# e-Tapperhandpiece18.net
KiCad netlist of a schematic drawn in EAGLE
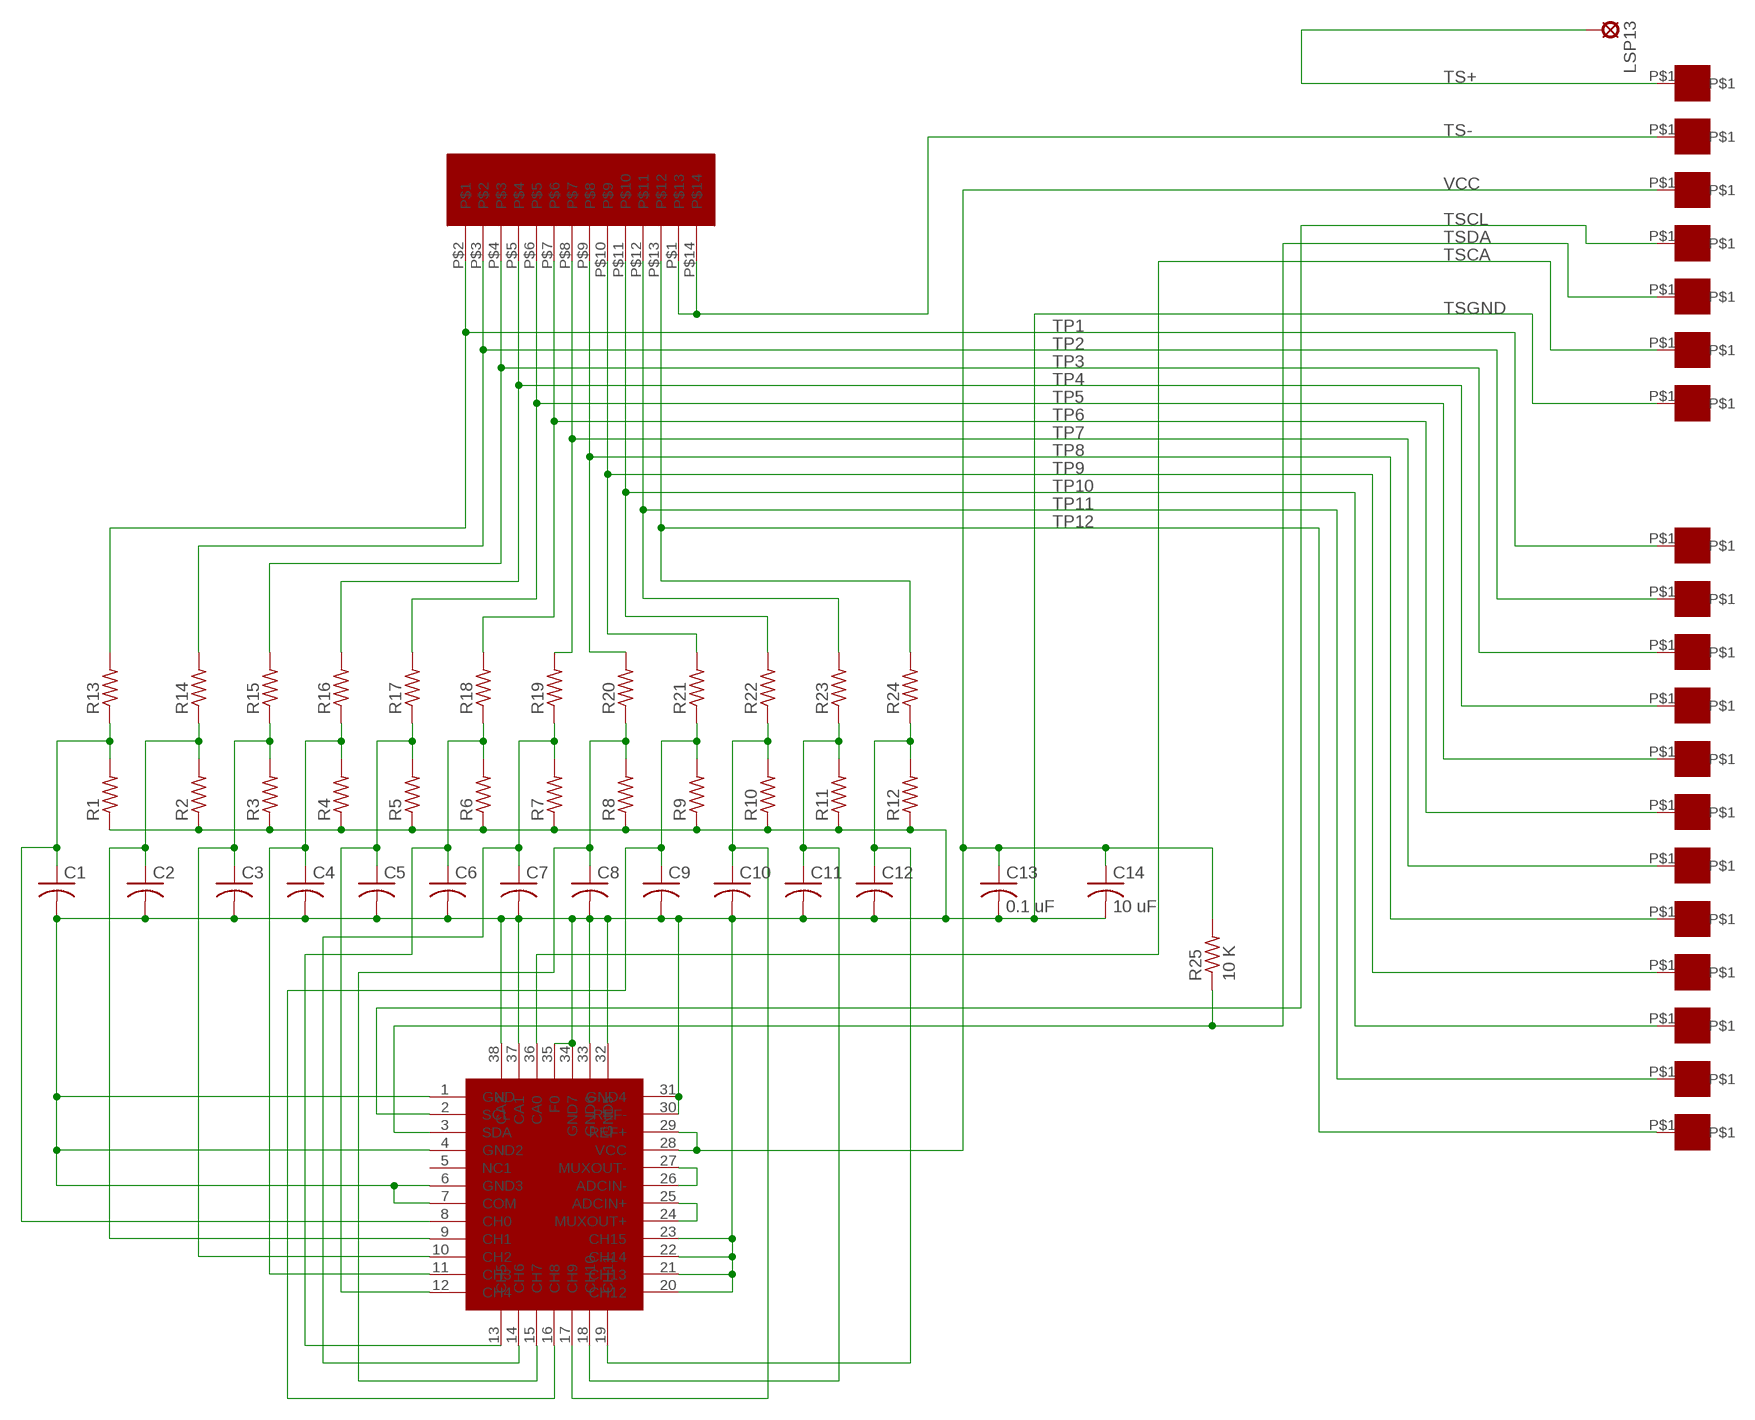
[diagram p0: schematic, sheet 1]

(export (version "E")
  (design (tool "Eeschema 10.0.6"))
  (components
    (comp (ref "C1")
      (value "C-USC0603")
      (footprint "eagle-import:C0603")
      (libsource (lib "eagle-import") (part "C-USC0603"))
    )
    (comp (ref "C2")
      (value "C-USC0603")
      (footprint "eagle-import:C0603")
      (libsource (lib "eagle-import") (part "C-USC0603"))
    )
    (comp (ref "C3")
      (value "C-USC0603")
      (footprint "eagle-import:C0603")
      (libsource (lib "eagle-import") (part "C-USC0603"))
    )
    (comp (ref "C4")
      (value "C-USC0603")
      (footprint "eagle-import:C0603")
      (libsource (lib "eagle-import") (part "C-USC0603"))
    )
    (comp (ref "C5")
      (value "C-USC0603")
      (footprint "eagle-import:C0603")
      (libsource (lib "eagle-import") (part "C-USC0603"))
    )
    (comp (ref "C6")
      (value "C-USC0603")
      (footprint "eagle-import:C0603")
      (libsource (lib "eagle-import") (part "C-USC0603"))
    )
    (comp (ref "C7")
      (value "C-USC0603")
      (footprint "eagle-import:C0603")
      (libsource (lib "eagle-import") (part "C-USC0603"))
    )
    (comp (ref "C8")
      (value "C-USC0603")
      (footprint "eagle-import:C0603")
      (libsource (lib "eagle-import") (part "C-USC0603"))
    )
    (comp (ref "C9")
      (value "C-USC0603")
      (footprint "eagle-import:C0603")
      (libsource (lib "eagle-import") (part "C-USC0603"))
    )
    (comp (ref "C10")
      (value "C-USC0603")
      (footprint "eagle-import:C0603")
      (libsource (lib "eagle-import") (part "C-USC0603"))
    )
    (comp (ref "C11")
      (value "C-USC0603")
      (footprint "eagle-import:C0603")
      (libsource (lib "eagle-import") (part "C-USC0603"))
    )
    (comp (ref "C12")
      (value "C-USC0603")
      (footprint "eagle-import:C0603")
      (libsource (lib "eagle-import") (part "C-USC0603"))
    )
    (comp (ref "C13")
      (value "0.1 uF")
      (footprint "eagle-import:C0603")
      (libsource (lib "eagle-import") (part "C-USC0603"))
    )
    (comp (ref "C14")
      (value "10 uF")
      (footprint "eagle-import:C0805")
      (libsource (lib "eagle-import") (part "C-USC0805"))
    )
    (comp (ref "LSP13")
      (value "SE11")
      (footprint "eagle-import:SE11")
      (libsource (lib "eagle-import") (part "SE11"))
    )
    (comp (ref "R1")
      (value "R-US_R0402")
      (footprint "eagle-import:R0402")
      (libsource (lib "eagle-import") (part "R-US_R0402"))
    )
    (comp (ref "R2")
      (value "R-US_R0402")
      (footprint "eagle-import:R0402")
      (libsource (lib "eagle-import") (part "R-US_R0402"))
    )
    (comp (ref "R3")
      (value "R-US_R0402")
      (footprint "eagle-import:R0402")
      (libsource (lib "eagle-import") (part "R-US_R0402"))
    )
    (comp (ref "R4")
      (value "R-US_R0402")
      (footprint "eagle-import:R0402")
      (libsource (lib "eagle-import") (part "R-US_R0402"))
    )
    (comp (ref "R5")
      (value "R-US_R0402")
      (footprint "eagle-import:R0402")
      (libsource (lib "eagle-import") (part "R-US_R0402"))
    )
    (comp (ref "R6")
      (value "R-US_R0402")
      (footprint "eagle-import:R0402")
      (libsource (lib "eagle-import") (part "R-US_R0402"))
    )
    (comp (ref "R7")
      (value "R-US_R0402")
      (footprint "eagle-import:R0402")
      (libsource (lib "eagle-import") (part "R-US_R0402"))
    )
    (comp (ref "R8")
      (value "R-US_R0402")
      (footprint "eagle-import:R0402")
      (libsource (lib "eagle-import") (part "R-US_R0402"))
    )
    (comp (ref "R9")
      (value "R-US_R0402")
      (footprint "eagle-import:R0402")
      (libsource (lib "eagle-import") (part "R-US_R0402"))
    )
    (comp (ref "R10")
      (value "R-US_R0402")
      (footprint "eagle-import:R0402")
      (libsource (lib "eagle-import") (part "R-US_R0402"))
    )
    (comp (ref "R11")
      (value "R-US_R0402")
      (footprint "eagle-import:R0402")
      (libsource (lib "eagle-import") (part "R-US_R0402"))
    )
    (comp (ref "R12")
      (value "R-US_R0402")
      (footprint "eagle-import:R0402")
      (libsource (lib "eagle-import") (part "R-US_R0402"))
    )
    (comp (ref "R13")
      (value "R-US_R0402")
      (footprint "eagle-import:R0402")
      (libsource (lib "eagle-import") (part "R-US_R0402"))
    )
    (comp (ref "R14")
      (value "R-US_R0402")
      (footprint "eagle-import:R0402")
      (libsource (lib "eagle-import") (part "R-US_R0402"))
    )
    (comp (ref "R15")
      (value "R-US_R0402")
      (footprint "eagle-import:R0402")
      (libsource (lib "eagle-import") (part "R-US_R0402"))
    )
    (comp (ref "R16")
      (value "R-US_R0402")
      (footprint "eagle-import:R0402")
      (libsource (lib "eagle-import") (part "R-US_R0402"))
    )
    (comp (ref "R17")
      (value "R-US_R0402")
      (footprint "eagle-import:R0402")
      (libsource (lib "eagle-import") (part "R-US_R0402"))
    )
    (comp (ref "R18")
      (value "R-US_R0402")
      (footprint "eagle-import:R0402")
      (libsource (lib "eagle-import") (part "R-US_R0402"))
    )
    (comp (ref "R19")
      (value "R-US_R0402")
      (footprint "eagle-import:R0402")
      (libsource (lib "eagle-import") (part "R-US_R0402"))
    )
    (comp (ref "R20")
      (value "R-US_R0402")
      (footprint "eagle-import:R0402")
      (libsource (lib "eagle-import") (part "R-US_R0402"))
    )
    (comp (ref "R21")
      (value "R-US_R0402")
      (footprint "eagle-import:R0402")
      (libsource (lib "eagle-import") (part "R-US_R0402"))
    )
    (comp (ref "R22")
      (value "R-US_R0402")
      (footprint "eagle-import:R0402")
      (libsource (lib "eagle-import") (part "R-US_R0402"))
    )
    (comp (ref "R23")
      (value "R-US_R0402")
      (footprint "eagle-import:R0402")
      (libsource (lib "eagle-import") (part "R-US_R0402"))
    )
    (comp (ref "R24")
      (value "R-US_R0402")
      (footprint "eagle-import:R0402")
      (libsource (lib "eagle-import") (part "R-US_R0402"))
    )
    (comp (ref "R25")
      (value "10 K")
      (footprint "eagle-import:R0402")
      (libsource (lib "eagle-import") (part "R-US_R0402"))
    )
    (comp (ref "TSP1")
      (value "ET1")
      (footprint "eagle-import:ET1")
      (libsource (lib "eagle-import") (part "ET1"))
    )
    (comp (ref "TSP2")
      (value "ET1")
      (footprint "eagle-import:ET1")
      (libsource (lib "eagle-import") (part "ET1"))
    )
    (comp (ref "TSP3")
      (value "ET1")
      (footprint "eagle-import:ET1")
      (libsource (lib "eagle-import") (part "ET1"))
    )
    (comp (ref "TSP4")
      (value "ET1")
      (footprint "eagle-import:ET1")
      (libsource (lib "eagle-import") (part "ET1"))
    )
    (comp (ref "TSP5")
      (value "ET1")
      (footprint "eagle-import:ET1")
      (libsource (lib "eagle-import") (part "ET1"))
    )
    (comp (ref "TSP6")
      (value "ET1")
      (footprint "eagle-import:ET1")
      (libsource (lib "eagle-import") (part "ET1"))
    )
    (comp (ref "TSP7")
      (value "ET1")
      (footprint "eagle-import:ET1")
      (libsource (lib "eagle-import") (part "ET1"))
    )
    (comp (ref "TSP8")
      (value "ET1")
      (footprint "eagle-import:ET1")
      (libsource (lib "eagle-import") (part "ET1"))
    )
    (comp (ref "TSP9")
      (value "ET1")
      (footprint "eagle-import:ET1")
      (libsource (lib "eagle-import") (part "ET1"))
    )
    (comp (ref "TSP10")
      (value "ET1")
      (footprint "eagle-import:ET1")
      (libsource (lib "eagle-import") (part "ET1"))
    )
    (comp (ref "TSP11")
      (value "ET1")
      (footprint "eagle-import:ET1")
      (libsource (lib "eagle-import") (part "ET1"))
    )
    (comp (ref "TSP12")
      (value "ET1")
      (footprint "eagle-import:ET1")
      (libsource (lib "eagle-import") (part "ET1"))
    )
    (comp (ref "TSP13")
      (value "ET1")
      (footprint "eagle-import:ET1")
      (libsource (lib "eagle-import") (part "ET1"))
    )
    (comp (ref "TSP14")
      (value "ET1")
      (footprint "eagle-import:ET1")
      (libsource (lib "eagle-import") (part "ET1"))
    )
    (comp (ref "TSP15")
      (value "ET1")
      (footprint "eagle-import:ET1")
      (libsource (lib "eagle-import") (part "ET1"))
    )
    (comp (ref "TSP16")
      (value "ET1")
      (footprint "eagle-import:ET1")
      (libsource (lib "eagle-import") (part "ET1"))
    )
    (comp (ref "TSP17")
      (value "ET1")
      (footprint "eagle-import:ET1")
      (libsource (lib "eagle-import") (part "ET1"))
    )
    (comp (ref "TSP18")
      (value "ET1")
      (footprint "eagle-import:ET1")
      (libsource (lib "eagle-import") (part "ET1"))
    )
    (comp (ref "TSP19")
      (value "ET1")
      (footprint "eagle-import:ET1")
      (libsource (lib "eagle-import") (part "ET1"))
    )
    (comp (ref "U$1")
      (value "LTC2497")
      (footprint "eagle-import:QFN38-5X7")
      (libsource (lib "eagle-import") (part "LTC2497"))
    )
    (comp (ref "U$2")
      (value "SS112D01")
      (footprint "eagle-import:SS112D01")
      (libsource (lib "eagle-import") (part "SS112D01"))
    )
  )
  (nets
    (net (code "1") (name "/TP1") (class "Default")
      (node (ref "R13") (pin "2") (pinfunction "2_2") (pintype "passive"))
      (node (ref "TSP1") (pin "P$1") (pinfunction "P$1_P$1") (pintype "bidirectional"))
      (node (ref "U$2") (pin "P$2") (pinfunction "P$1_P$2") (pintype "bidirectional"))
    )
    (net (code "2") (name "/TP2") (class "Default")
      (node (ref "R14") (pin "2") (pinfunction "2_2") (pintype "passive"))
      (node (ref "TSP2") (pin "P$1") (pinfunction "P$1_P$1") (pintype "bidirectional"))
      (node (ref "U$2") (pin "P$3") (pinfunction "P$2_P$3") (pintype "bidirectional"))
    )
    (net (code "3") (name "/TP3") (class "Default")
      (node (ref "R15") (pin "2") (pinfunction "2_2") (pintype "passive"))
      (node (ref "TSP3") (pin "P$1") (pinfunction "P$1_P$1") (pintype "bidirectional"))
      (node (ref "U$2") (pin "P$4") (pinfunction "P$3_P$4") (pintype "bidirectional"))
    )
    (net (code "4") (name "/TP4") (class "Default")
      (node (ref "R16") (pin "2") (pinfunction "2_2") (pintype "passive"))
      (node (ref "TSP4") (pin "P$1") (pinfunction "P$1_P$1") (pintype "bidirectional"))
      (node (ref "U$2") (pin "P$5") (pinfunction "P$4_P$5") (pintype "bidirectional"))
    )
    (net (code "5") (name "/TP5") (class "Default")
      (node (ref "R17") (pin "2") (pinfunction "2_2") (pintype "passive"))
      (node (ref "TSP5") (pin "P$1") (pinfunction "P$1_P$1") (pintype "bidirectional"))
      (node (ref "U$2") (pin "P$6") (pinfunction "P$5_P$6") (pintype "bidirectional"))
    )
    (net (code "6") (name "/TP6") (class "Default")
      (node (ref "R18") (pin "2") (pinfunction "2_2") (pintype "passive"))
      (node (ref "TSP6") (pin "P$1") (pinfunction "P$1_P$1") (pintype "bidirectional"))
      (node (ref "U$2") (pin "P$7") (pinfunction "P$6_P$7") (pintype "bidirectional"))
    )
    (net (code "7") (name "/TP7") (class "Default")
      (node (ref "R19") (pin "2") (pinfunction "2_2") (pintype "passive"))
      (node (ref "TSP7") (pin "P$1") (pinfunction "P$1_P$1") (pintype "bidirectional"))
      (node (ref "U$2") (pin "P$8") (pinfunction "P$7_P$8") (pintype "bidirectional"))
    )
    (net (code "8") (name "/TP8") (class "Default")
      (node (ref "R20") (pin "2") (pinfunction "2_2") (pintype "passive"))
      (node (ref "TSP8") (pin "P$1") (pinfunction "P$1_P$1") (pintype "bidirectional"))
      (node (ref "U$2") (pin "P$9") (pinfunction "P$8_P$9") (pintype "bidirectional"))
    )
    (net (code "9") (name "/TP9") (class "Default")
      (node (ref "R21") (pin "2") (pinfunction "2_2") (pintype "passive"))
      (node (ref "TSP9") (pin "P$1") (pinfunction "P$1_P$1") (pintype "bidirectional"))
      (node (ref "U$2") (pin "P$10") (pinfunction "P$9_P$10") (pintype "bidirectional"))
    )
    (net (code "10") (name "/TP10") (class "Default")
      (node (ref "R22") (pin "2") (pinfunction "2_2") (pintype "passive"))
      (node (ref "TSP10") (pin "P$1") (pinfunction "P$1_P$1") (pintype "bidirectional"))
      (node (ref "U$2") (pin "P$11") (pinfunction "P$10_P$11") (pintype "bidirectional"))
    )
    (net (code "11") (name "/TP11") (class "Default")
      (node (ref "R23") (pin "2") (pinfunction "2_2") (pintype "passive"))
      (node (ref "TSP11") (pin "P$1") (pinfunction "P$1_P$1") (pintype "bidirectional"))
      (node (ref "U$2") (pin "P$12") (pinfunction "P$11_P$12") (pintype "bidirectional"))
    )
    (net (code "12") (name "/TP12") (class "Default")
      (node (ref "R24") (pin "2") (pinfunction "2_2") (pintype "passive"))
      (node (ref "TSP12") (pin "P$1") (pinfunction "P$1_P$1") (pintype "bidirectional"))
      (node (ref "U$2") (pin "P$13") (pinfunction "P$12_P$13") (pintype "bidirectional"))
    )
    (net (code "13") (name "/TS+") (class "Default")
      (node (ref "LSP13") (pin "MP") (pinfunction "MP_MP") (pintype "passive"))
      (node (ref "TSP13") (pin "P$1") (pinfunction "P$1_P$1") (pintype "bidirectional"))
    )
    (net (code "14") (name "/TS-") (class "Default")
      (node (ref "TSP14") (pin "P$1") (pinfunction "P$1_P$1") (pintype "bidirectional"))
      (node (ref "U$2") (pin "P$1") (pinfunction "P$13_P$1") (pintype "bidirectional"))
      (node (ref "U$2") (pin "P$14") (pinfunction "P$14_P$14") (pintype "bidirectional"))
    )
    (net (code "15") (name "/TSCA") (class "Default")
      (node (ref "TSP18") (pin "P$1") (pinfunction "P$1_P$1") (pintype "bidirectional"))
      (node (ref "U$1") (pin "36") (pinfunction "CA0_36") (pintype "bidirectional"))
    )
    (net (code "16") (name "/TSCL") (class "Default")
      (node (ref "TSP16") (pin "P$1") (pinfunction "P$1_P$1") (pintype "bidirectional"))
      (node (ref "U$1") (pin "2") (pinfunction "SCL_2") (pintype "bidirectional"))
    )
    (net (code "17") (name "/TSDA") (class "Default")
      (node (ref "R25") (pin "1") (pinfunction "1_1") (pintype "passive"))
      (node (ref "TSP17") (pin "P$1") (pinfunction "P$1_P$1") (pintype "bidirectional"))
      (node (ref "U$1") (pin "3") (pinfunction "SDA_3") (pintype "bidirectional"))
    )
    (net (code "18") (name "/TSGND") (class "Default")
      (node (ref "C1") (pin "2") (pinfunction "2_2") (pintype "passive"))
      (node (ref "C10") (pin "2") (pinfunction "2_2") (pintype "passive"))
      (node (ref "C11") (pin "2") (pinfunction "2_2") (pintype "passive"))
      (node (ref "C12") (pin "2") (pinfunction "2_2") (pintype "passive"))
      (node (ref "C13") (pin "2") (pinfunction "2_2") (pintype "passive"))
      (node (ref "C14") (pin "2") (pinfunction "2_2") (pintype "passive"))
      (node (ref "C2") (pin "2") (pinfunction "2_2") (pintype "passive"))
      (node (ref "C3") (pin "2") (pinfunction "2_2") (pintype "passive"))
      (node (ref "C4") (pin "2") (pinfunction "2_2") (pintype "passive"))
      (node (ref "C5") (pin "2") (pinfunction "2_2") (pintype "passive"))
      (node (ref "C6") (pin "2") (pinfunction "2_2") (pintype "passive"))
      (node (ref "C7") (pin "2") (pinfunction "2_2") (pintype "passive"))
      (node (ref "C8") (pin "2") (pinfunction "2_2") (pintype "passive"))
      (node (ref "C9") (pin "2") (pinfunction "2_2") (pintype "passive"))
      (node (ref "R1") (pin "1") (pinfunction "1_1") (pintype "passive"))
      (node (ref "R10") (pin "1") (pinfunction "1_1") (pintype "passive"))
      (node (ref "R11") (pin "1") (pinfunction "1_1") (pintype "passive"))
      (node (ref "R12") (pin "1") (pinfunction "1_1") (pintype "passive"))
      (node (ref "R2") (pin "1") (pinfunction "1_1") (pintype "passive"))
      (node (ref "R3") (pin "1") (pinfunction "1_1") (pintype "passive"))
      (node (ref "R4") (pin "1") (pinfunction "1_1") (pintype "passive"))
      (node (ref "R5") (pin "1") (pinfunction "1_1") (pintype "passive"))
      (node (ref "R6") (pin "1") (pinfunction "1_1") (pintype "passive"))
      (node (ref "R7") (pin "1") (pinfunction "1_1") (pintype "passive"))
      (node (ref "R8") (pin "1") (pinfunction "1_1") (pintype "passive"))
      (node (ref "R9") (pin "1") (pinfunction "1_1") (pintype "passive"))
      (node (ref "TSP19") (pin "P$1") (pinfunction "P$1_P$1") (pintype "bidirectional"))
      (node (ref "U$1") (pin "1") (pinfunction "GND_1") (pintype "power_in"))
      (node (ref "U$1") (pin "20") (pinfunction "CH12_20") (pintype "input"))
      (node (ref "U$1") (pin "21") (pinfunction "CH13_21") (pintype "input"))
      (node (ref "U$1") (pin "22") (pinfunction "CH14_22") (pintype "input"))
      (node (ref "U$1") (pin "23") (pinfunction "CH15_23") (pintype "input"))
      (node (ref "U$1") (pin "30") (pinfunction "REF-_30") (pintype "bidirectional"))
      (node (ref "U$1") (pin "31") (pinfunction "GND4_31") (pintype "power_in"))
      (node (ref "U$1") (pin "32") (pinfunction "GND5_32") (pintype "power_in"))
      (node (ref "U$1") (pin "33") (pinfunction "GND6_33") (pintype "power_in"))
      (node (ref "U$1") (pin "34") (pinfunction "GND7_34") (pintype "power_in"))
      (node (ref "U$1") (pin "35") (pinfunction "F0_35") (pintype "bidirectional"))
      (node (ref "U$1") (pin "37") (pinfunction "CA1_37") (pintype "bidirectional"))
      (node (ref "U$1") (pin "38") (pinfunction "CA2_38") (pintype "bidirectional"))
      (node (ref "U$1") (pin "4") (pinfunction "GND2_4") (pintype "power_in"))
      (node (ref "U$1") (pin "6") (pinfunction "GND3_6") (pintype "power_in"))
      (node (ref "U$1") (pin "7") (pinfunction "COM_7") (pintype "power_in"))
    )
    (net (code "19") (name "/VCC") (class "Default")
      (node (ref "C13") (pin "1") (pinfunction "1_1") (pintype "passive"))
      (node (ref "C14") (pin "1") (pinfunction "1_1") (pintype "passive"))
      (node (ref "R25") (pin "2") (pinfunction "2_2") (pintype "passive"))
      (node (ref "TSP15") (pin "P$1") (pinfunction "P$1_P$1") (pintype "bidirectional"))
      (node (ref "U$1") (pin "28") (pinfunction "VCC_28") (pintype "power_in"))
      (node (ref "U$1") (pin "29") (pinfunction "REF+_29") (pintype "bidirectional"))
    )
    (net (code "20") (name "Net-(U$1-ADCIN+)") (class "Default")
      (node (ref "U$1") (pin "24") (pinfunction "MUXOUT+_24") (pintype "bidirectional"))
      (node (ref "U$1") (pin "25") (pinfunction "ADCIN+_25") (pintype "bidirectional"))
    )
    (net (code "21") (name "Net-(U$1-ADCIN-)") (class "Default")
      (node (ref "U$1") (pin "26") (pinfunction "ADCIN-_26") (pintype "bidirectional"))
      (node (ref "U$1") (pin "27") (pinfunction "MUXOUT-_27") (pintype "bidirectional"))
    )
    (net (code "22") (name "Net-(U$1-CH0)") (class "Default")
      (node (ref "C1") (pin "1") (pinfunction "1_1") (pintype "passive"))
      (node (ref "R1") (pin "2") (pinfunction "2_2") (pintype "passive"))
      (node (ref "R13") (pin "1") (pinfunction "1_1") (pintype "passive"))
      (node (ref "U$1") (pin "8") (pinfunction "CH0_8") (pintype "input"))
    )
    (net (code "23") (name "Net-(U$1-CH1)") (class "Default")
      (node (ref "C2") (pin "1") (pinfunction "1_1") (pintype "passive"))
      (node (ref "R14") (pin "1") (pinfunction "1_1") (pintype "passive"))
      (node (ref "R2") (pin "2") (pinfunction "2_2") (pintype "passive"))
      (node (ref "U$1") (pin "9") (pinfunction "CH1_9") (pintype "input"))
    )
    (net (code "24") (name "Net-(U$1-CH2)") (class "Default")
      (node (ref "C3") (pin "1") (pinfunction "1_1") (pintype "passive"))
      (node (ref "R15") (pin "1") (pinfunction "1_1") (pintype "passive"))
      (node (ref "R3") (pin "2") (pinfunction "2_2") (pintype "passive"))
      (node (ref "U$1") (pin "10") (pinfunction "CH2_10") (pintype "input"))
    )
    (net (code "25") (name "Net-(U$1-CH3)") (class "Default")
      (node (ref "C4") (pin "1") (pinfunction "1_1") (pintype "passive"))
      (node (ref "R16") (pin "1") (pinfunction "1_1") (pintype "passive"))
      (node (ref "R4") (pin "2") (pinfunction "2_2") (pintype "passive"))
      (node (ref "U$1") (pin "11") (pinfunction "CH3_11") (pintype "input"))
    )
    (net (code "26") (name "Net-(U$1-CH4)") (class "Default")
      (node (ref "C5") (pin "1") (pinfunction "1_1") (pintype "passive"))
      (node (ref "R17") (pin "1") (pinfunction "1_1") (pintype "passive"))
      (node (ref "R5") (pin "2") (pinfunction "2_2") (pintype "passive"))
      (node (ref "U$1") (pin "12") (pinfunction "CH4_12") (pintype "input"))
    )
    (net (code "27") (name "Net-(U$1-CH5)") (class "Default")
      (node (ref "C6") (pin "1") (pinfunction "1_1") (pintype "passive"))
      (node (ref "R18") (pin "1") (pinfunction "1_1") (pintype "passive"))
      (node (ref "R6") (pin "2") (pinfunction "2_2") (pintype "passive"))
      (node (ref "U$1") (pin "13") (pinfunction "CH5_13") (pintype "input"))
    )
    (net (code "28") (name "Net-(U$1-CH6)") (class "Default")
      (node (ref "C7") (pin "1") (pinfunction "1_1") (pintype "passive"))
      (node (ref "R19") (pin "1") (pinfunction "1_1") (pintype "passive"))
      (node (ref "R7") (pin "2") (pinfunction "2_2") (pintype "passive"))
      (node (ref "U$1") (pin "14") (pinfunction "CH6_14") (pintype "input"))
    )
    (net (code "29") (name "Net-(U$1-CH7)") (class "Default")
      (node (ref "C8") (pin "1") (pinfunction "1_1") (pintype "passive"))
      (node (ref "R20") (pin "1") (pinfunction "1_1") (pintype "passive"))
      (node (ref "R8") (pin "2") (pinfunction "2_2") (pintype "passive"))
      (node (ref "U$1") (pin "15") (pinfunction "CH7_15") (pintype "input"))
    )
    (net (code "30") (name "Net-(U$1-CH8)") (class "Default")
      (node (ref "C9") (pin "1") (pinfunction "1_1") (pintype "passive"))
      (node (ref "R21") (pin "1") (pinfunction "1_1") (pintype "passive"))
      (node (ref "R9") (pin "2") (pinfunction "2_2") (pintype "passive"))
      (node (ref "U$1") (pin "16") (pinfunction "CH8_16") (pintype "input"))
    )
    (net (code "31") (name "Net-(U$1-CH9)") (class "Default")
      (node (ref "C10") (pin "1") (pinfunction "1_1") (pintype "passive"))
      (node (ref "R10") (pin "2") (pinfunction "2_2") (pintype "passive"))
      (node (ref "R22") (pin "1") (pinfunction "1_1") (pintype "passive"))
      (node (ref "U$1") (pin "17") (pinfunction "CH9_17") (pintype "input"))
    )
    (net (code "32") (name "Net-(U$1-CH10)") (class "Default")
      (node (ref "C11") (pin "1") (pinfunction "1_1") (pintype "passive"))
      (node (ref "R11") (pin "2") (pinfunction "2_2") (pintype "passive"))
      (node (ref "R23") (pin "1") (pinfunction "1_1") (pintype "passive"))
      (node (ref "U$1") (pin "18") (pinfunction "CH10_18") (pintype "input"))
    )
    (net (code "33") (name "Net-(U$1-CH11)") (class "Default")
      (node (ref "C12") (pin "1") (pinfunction "1_1") (pintype "passive"))
      (node (ref "R12") (pin "2") (pinfunction "2_2") (pintype "passive"))
      (node (ref "R24") (pin "1") (pinfunction "1_1") (pintype "passive"))
      (node (ref "U$1") (pin "19") (pinfunction "CH11_19") (pintype "input"))
    )
    (net (code "34") (name "unconnected-(U$1-NC1-Pad5)") (class "Default")
      (node (ref "U$1") (pin "5") (pinfunction "NC1_5") (pintype "no_connect"))
    )
  )
)
